# adxrs300_breakout.net
KiCad netlist of a schematic drawn in EAGLE
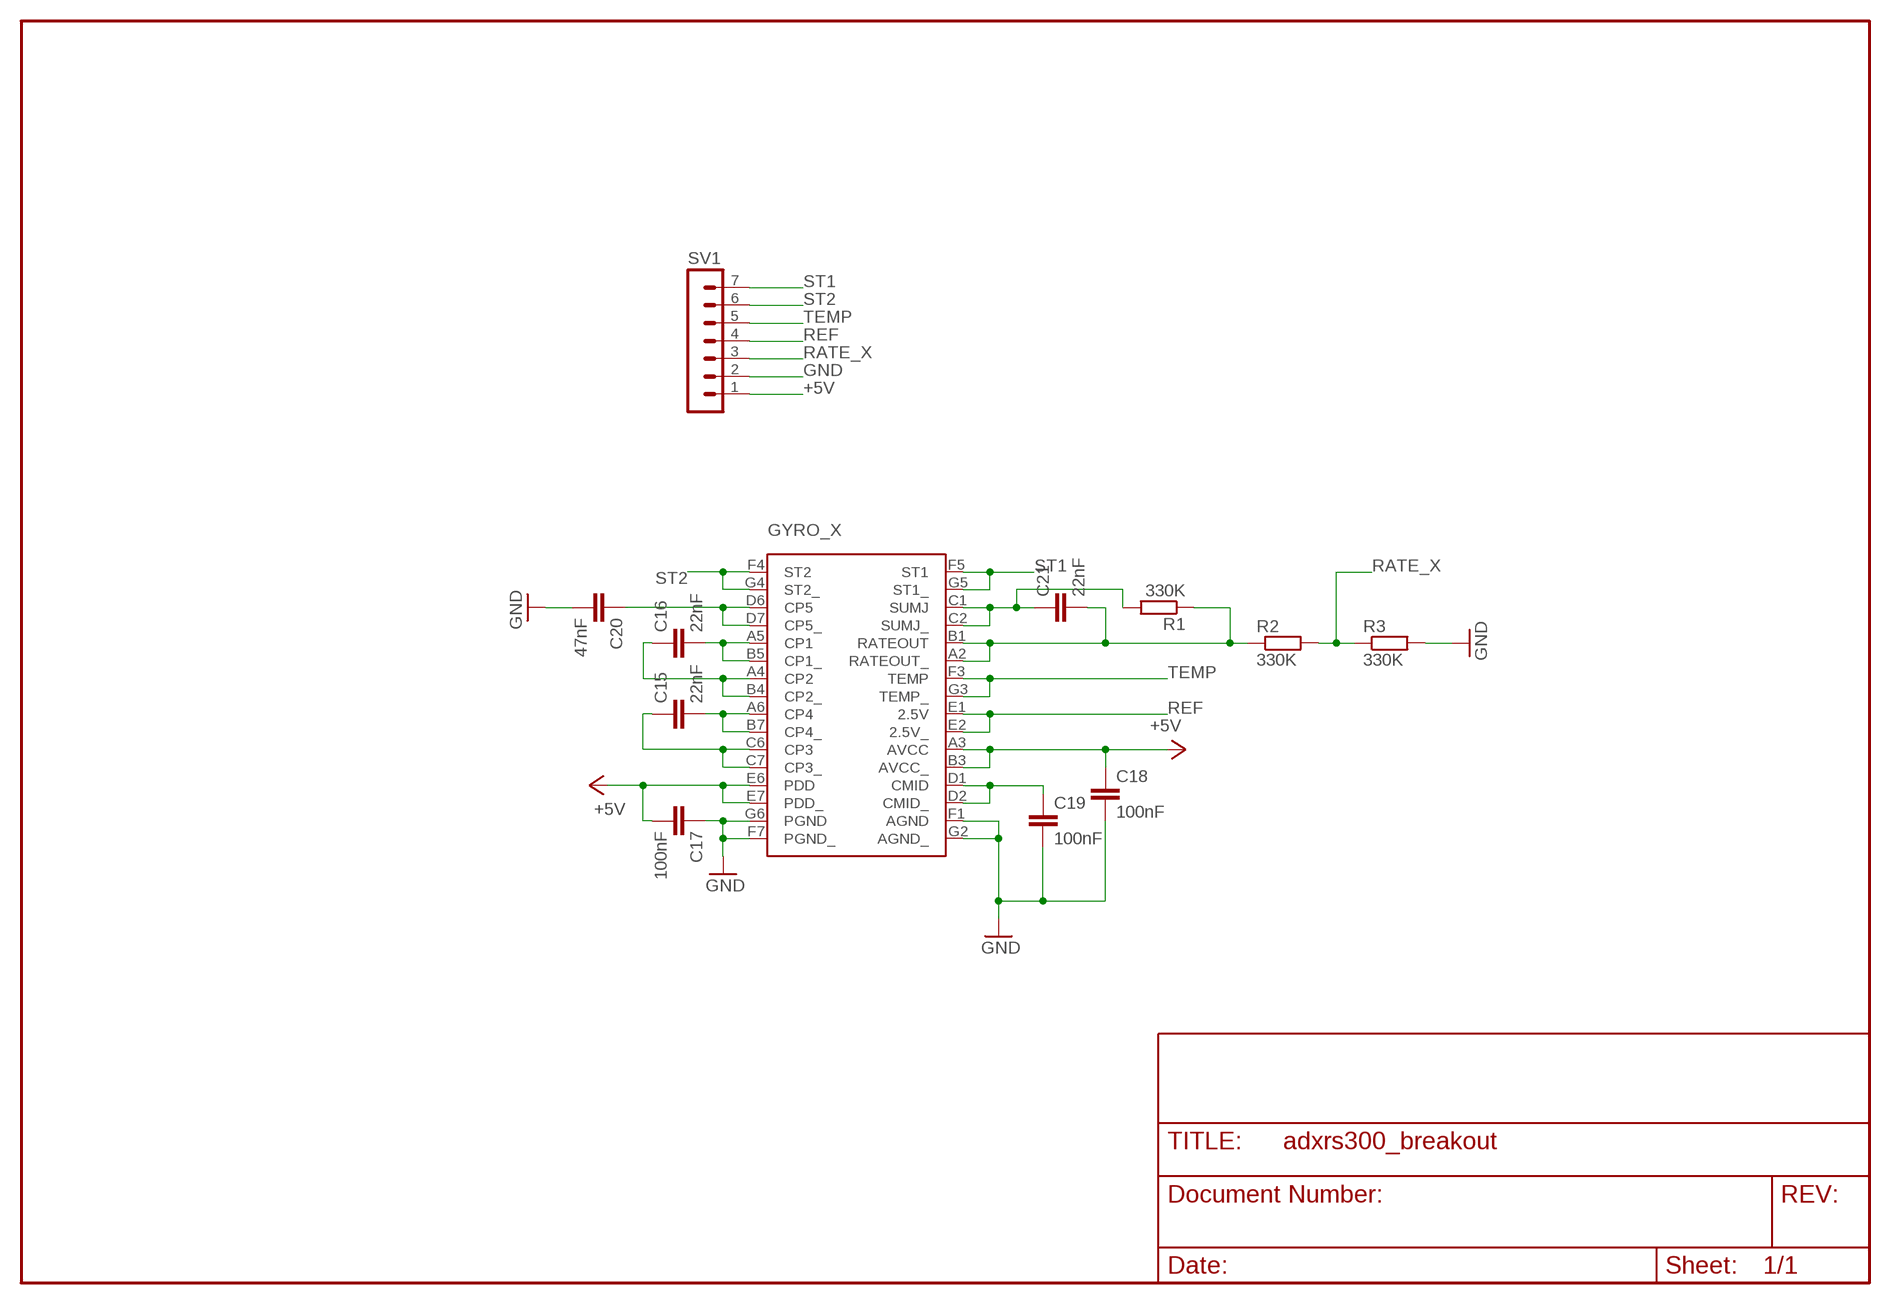
[diagram p0: schematic, sheet 1]

(export (version "E")
  (design (tool "Eeschema 10.0.6"))
  (components
    (comp (ref "C15")
      (value "22nF")
      (footprint "eagle-import:C0603K")
      (libsource (lib "eagle-import") (part "C-EUC0603K"))
    )
    (comp (ref "C16")
      (value "22nF")
      (footprint "eagle-import:C0603K")
      (libsource (lib "eagle-import") (part "C-EUC0603K"))
    )
    (comp (ref "C17")
      (value "100nF")
      (footprint "eagle-import:C0603K")
      (libsource (lib "eagle-import") (part "C-EUC0603K"))
    )
    (comp (ref "C18")
      (value "100nF")
      (footprint "eagle-import:C0603K")
      (libsource (lib "eagle-import") (part "C-EUC0603K"))
    )
    (comp (ref "C19")
      (value "100nF")
      (footprint "eagle-import:C0603K")
      (libsource (lib "eagle-import") (part "C-EUC0603K"))
    )
    (comp (ref "C20")
      (value "47nF")
      (footprint "eagle-import:C0603K")
      (libsource (lib "eagle-import") (part "C-EUC0603K"))
    )
    (comp (ref "C21")
      (value "22nF")
      (footprint "eagle-import:C0603K")
      (libsource (lib "eagle-import") (part "C-EUC0603K"))
    )
    (comp (ref "GYRO_X")
      (value "ADXR")
      (footprint "eagle-import:BC-32")
      (libsource (lib "eagle-import") (part "ADXR"))
    )
    (comp (ref "R1")
      (value "330K")
      (footprint "eagle-import:R0603")
      (libsource (lib "eagle-import") (part "R-EU_R0603"))
    )
    (comp (ref "R2")
      (value "330K")
      (footprint "eagle-import:R0603")
      (libsource (lib "eagle-import") (part "R-EU_R0603"))
    )
    (comp (ref "R3")
      (value "330K")
      (footprint "eagle-import:R0603")
      (libsource (lib "eagle-import") (part "R-EU_R0603"))
    )
    (comp (ref "SV1")
      (value "MA07-1")
      (footprint "eagle-import:MA07-1")
      (libsource (lib "eagle-import") (part "MA07-1"))
    )
  )
  (nets
    (net (code "1") (name "+5V") (class "Default")
      (node (ref "C17") (pin "2") (pinfunction "2_2") (pintype "passive"))
      (node (ref "C18") (pin "1") (pinfunction "1_1") (pintype "passive"))
      (node (ref "GYRO_X") (pin "A3") (pinfunction "AVCC_A3") (pintype "bidirectional"))
      (node (ref "GYRO_X") (pin "B3") (pinfunction "AVCC__B3") (pintype "bidirectional"))
      (node (ref "GYRO_X") (pin "E6") (pinfunction "PDD_E6") (pintype "bidirectional"))
      (node (ref "GYRO_X") (pin "E7") (pinfunction "PDD__E7") (pintype "bidirectional"))
      (node (ref "SV1") (pin "1") (pinfunction "1_1") (pintype "passive"))
    )
    (net (code "2") (name "/RATE_X") (class "Default")
      (node (ref "R2") (pin "2") (pinfunction "2_2") (pintype "passive"))
      (node (ref "R3") (pin "1") (pinfunction "1_1") (pintype "passive"))
      (node (ref "SV1") (pin "3") (pinfunction "3_3") (pintype "passive"))
    )
    (net (code "3") (name "/REF") (class "Default")
      (node (ref "GYRO_X") (pin "E1") (pinfunction "2.5V_E1") (pintype "bidirectional"))
      (node (ref "GYRO_X") (pin "E2") (pinfunction "2.5V__E2") (pintype "bidirectional"))
      (node (ref "SV1") (pin "4") (pinfunction "4_4") (pintype "passive"))
    )
    (net (code "4") (name "/ST1") (class "Default")
      (node (ref "GYRO_X") (pin "F5") (pinfunction "ST1_F5") (pintype "bidirectional"))
      (node (ref "GYRO_X") (pin "G5") (pinfunction "ST1__G5") (pintype "bidirectional"))
      (node (ref "SV1") (pin "7") (pinfunction "7_7") (pintype "passive"))
    )
    (net (code "5") (name "/ST2") (class "Default")
      (node (ref "GYRO_X") (pin "F4") (pinfunction "ST2_F4") (pintype "bidirectional"))
      (node (ref "GYRO_X") (pin "G4") (pinfunction "ST2__G4") (pintype "bidirectional"))
      (node (ref "SV1") (pin "6") (pinfunction "6_6") (pintype "passive"))
    )
    (net (code "6") (name "/TEMP") (class "Default")
      (node (ref "GYRO_X") (pin "F3") (pinfunction "TEMP_F3") (pintype "bidirectional"))
      (node (ref "GYRO_X") (pin "G3") (pinfunction "TEMP__G3") (pintype "bidirectional"))
      (node (ref "SV1") (pin "5") (pinfunction "5_5") (pintype "passive"))
    )
    (net (code "7") (name "GND") (class "Default")
      (node (ref "C17") (pin "1") (pinfunction "1_1") (pintype "passive"))
      (node (ref "C18") (pin "2") (pinfunction "2_2") (pintype "passive"))
      (node (ref "C19") (pin "2") (pinfunction "2_2") (pintype "passive"))
      (node (ref "C20") (pin "2") (pinfunction "2_2") (pintype "passive"))
      (node (ref "GYRO_X") (pin "F1") (pinfunction "AGND_F1") (pintype "bidirectional"))
      (node (ref "GYRO_X") (pin "F7") (pinfunction "PGND__F7") (pintype "bidirectional"))
      (node (ref "GYRO_X") (pin "G2") (pinfunction "AGND__G2") (pintype "bidirectional"))
      (node (ref "GYRO_X") (pin "G6") (pinfunction "PGND_G6") (pintype "bidirectional"))
      (node (ref "R3") (pin "2") (pinfunction "2_2") (pintype "passive"))
      (node (ref "SV1") (pin "2") (pinfunction "2_2") (pintype "passive"))
    )
    (net (code "8") (name "Net-(GYRO_X-CMID)") (class "Default")
      (node (ref "C19") (pin "1") (pinfunction "1_1") (pintype "passive"))
      (node (ref "GYRO_X") (pin "D1") (pinfunction "CMID_D1") (pintype "bidirectional"))
      (node (ref "GYRO_X") (pin "D2") (pinfunction "CMID__D2") (pintype "bidirectional"))
    )
    (net (code "9") (name "Net-(GYRO_X-CP1)") (class "Default")
      (node (ref "C16") (pin "2") (pinfunction "2_2") (pintype "passive"))
      (node (ref "GYRO_X") (pin "A5") (pinfunction "CP1_A5") (pintype "bidirectional"))
      (node (ref "GYRO_X") (pin "B5") (pinfunction "CP1__B5") (pintype "bidirectional"))
    )
    (net (code "10") (name "Net-(GYRO_X-CP2)") (class "Default")
      (node (ref "C16") (pin "1") (pinfunction "1_1") (pintype "passive"))
      (node (ref "GYRO_X") (pin "A4") (pinfunction "CP2_A4") (pintype "bidirectional"))
      (node (ref "GYRO_X") (pin "B4") (pinfunction "CP2__B4") (pintype "bidirectional"))
    )
    (net (code "11") (name "Net-(GYRO_X-CP3)") (class "Default")
      (node (ref "C15") (pin "1") (pinfunction "1_1") (pintype "passive"))
      (node (ref "GYRO_X") (pin "C6") (pinfunction "CP3_C6") (pintype "bidirectional"))
      (node (ref "GYRO_X") (pin "C7") (pinfunction "CP3__C7") (pintype "bidirectional"))
    )
    (net (code "12") (name "Net-(GYRO_X-CP4)") (class "Default")
      (node (ref "C15") (pin "2") (pinfunction "2_2") (pintype "passive"))
      (node (ref "GYRO_X") (pin "A6") (pinfunction "CP4_A6") (pintype "bidirectional"))
      (node (ref "GYRO_X") (pin "B7") (pinfunction "CP4__B7") (pintype "bidirectional"))
    )
    (net (code "13") (name "Net-(GYRO_X-CP5)") (class "Default")
      (node (ref "C20") (pin "1") (pinfunction "1_1") (pintype "passive"))
      (node (ref "GYRO_X") (pin "D6") (pinfunction "CP5_D6") (pintype "bidirectional"))
      (node (ref "GYRO_X") (pin "D7") (pinfunction "CP5__D7") (pintype "bidirectional"))
    )
    (net (code "14") (name "Net-(GYRO_X-RATEOUT)") (class "Default")
      (node (ref "C21") (pin "2") (pinfunction "2_2") (pintype "passive"))
      (node (ref "GYRO_X") (pin "A2") (pinfunction "RATEOUT__A2") (pintype "bidirectional"))
      (node (ref "GYRO_X") (pin "B1") (pinfunction "RATEOUT_B1") (pintype "bidirectional"))
      (node (ref "R1") (pin "1") (pinfunction "1_1") (pintype "passive"))
      (node (ref "R2") (pin "1") (pinfunction "1_1") (pintype "passive"))
    )
    (net (code "15") (name "Net-(GYRO_X-SUMJ)") (class "Default")
      (node (ref "C21") (pin "1") (pinfunction "1_1") (pintype "passive"))
      (node (ref "GYRO_X") (pin "C1") (pinfunction "SUMJ_C1") (pintype "bidirectional"))
      (node (ref "GYRO_X") (pin "C2") (pinfunction "SUMJ__C2") (pintype "bidirectional"))
      (node (ref "R1") (pin "2") (pinfunction "2_2") (pintype "passive"))
    )
  )
)
